# Power-Supplies.net
KiCad netlist of a schematic drawn in Altium Designer
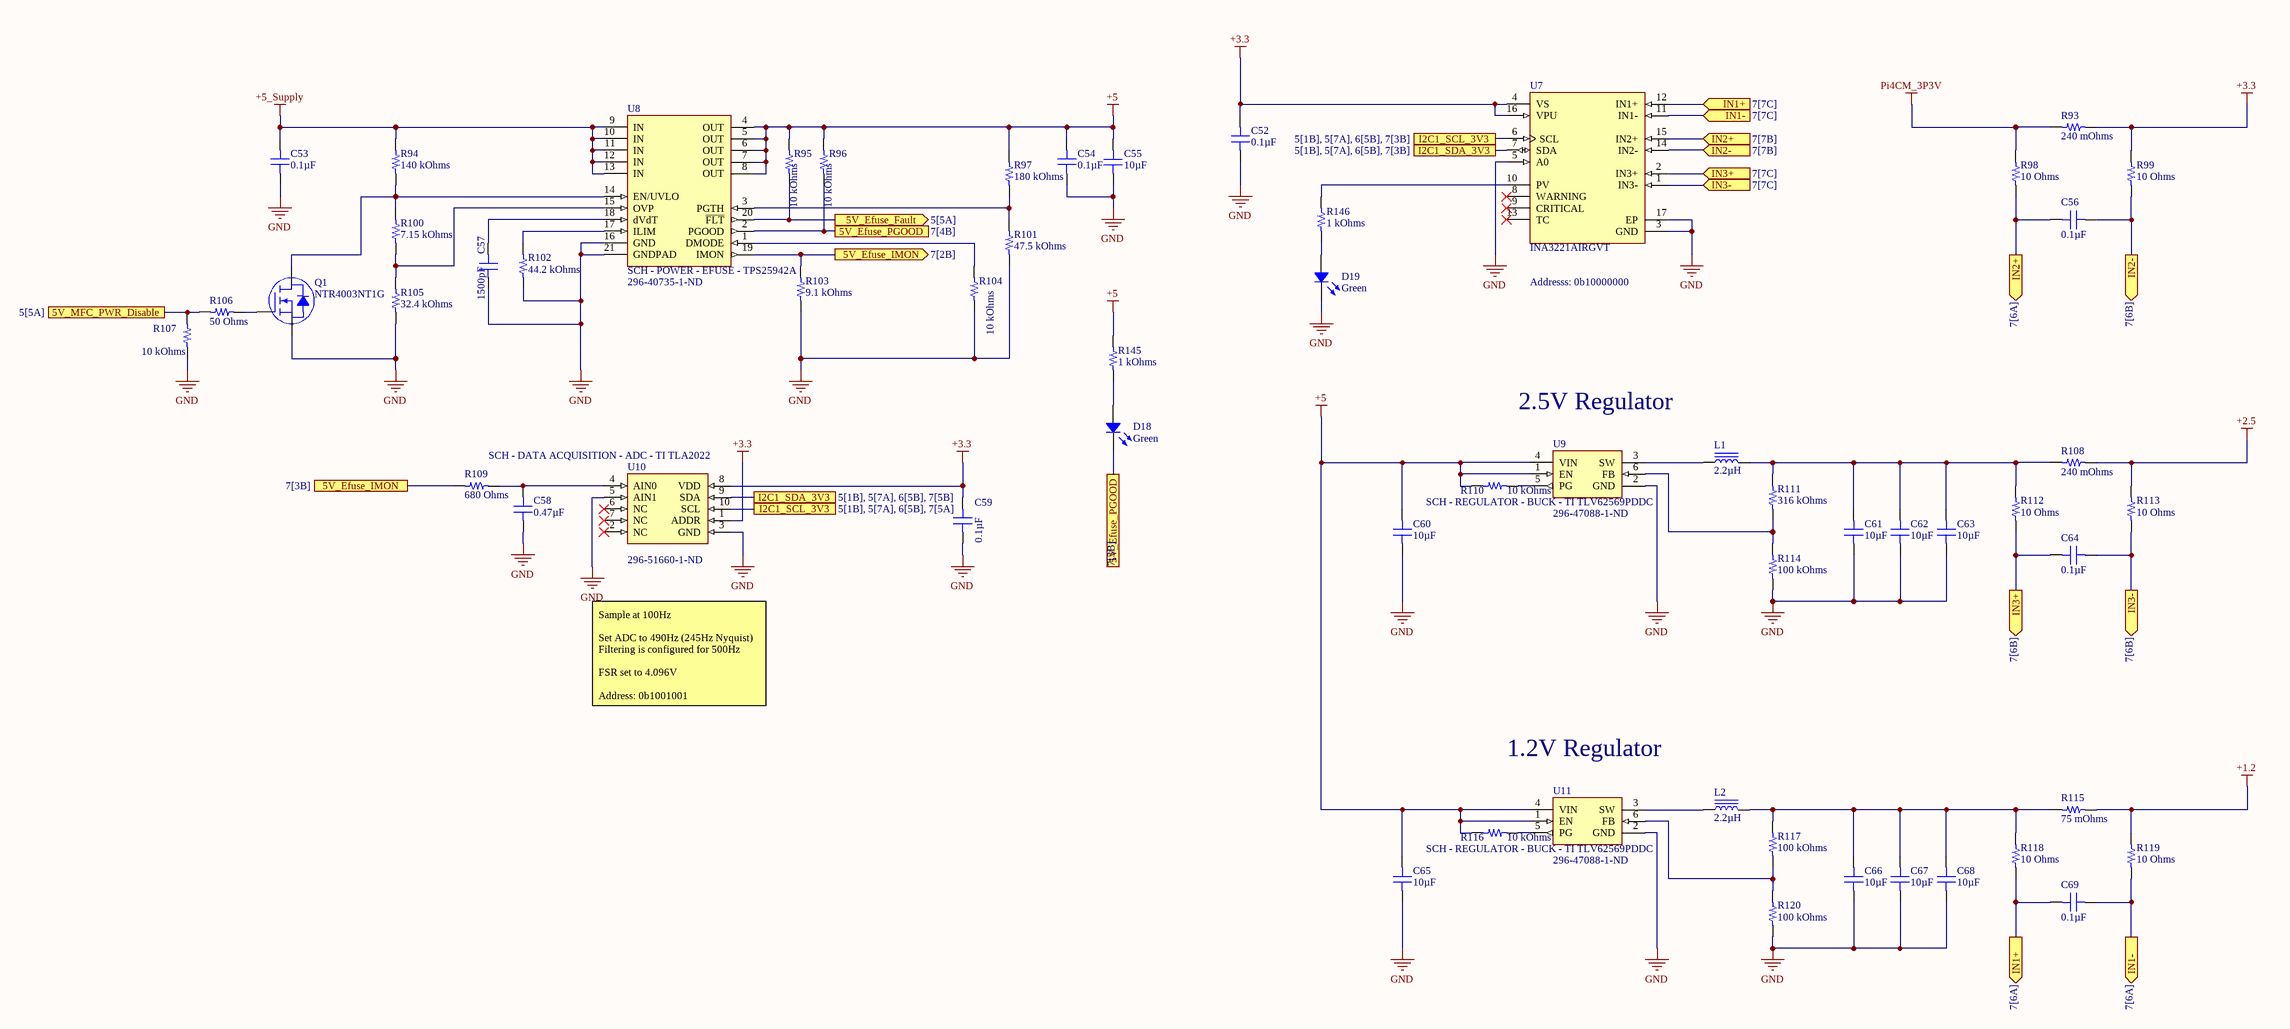
[diagram p0: Power-Supplies.SchDoc]

(export (version "E")
  (design (tool "Eeschema 10.0.6"))
  (components
    (comp (ref "C52")
      (value "0.1µF")
      (footprint "CAP 0603_1608")
      (description "CAP CER 0.1UF 25V X7R 0603")
      (fields
        (field (name "PART NUMBER") "CL10B104KA8WPNC")
        (field (name "MANUFACTURER") "Samsung Electro-Mechanics")
      )
      (libsource (lib "Celestial Altium Library - altium_library") (part "Capacitor"))
    )
    (comp (ref "C53")
      (value "0.1µF")
      (footprint "CAP 0603_1608")
      (description "CAP CER 0.1UF 25V X7R 0603")
      (fields
        (field (name "PART NUMBER") "CL10B104KA8WPNC")
        (field (name "MANUFACTURER") "Samsung Electro-Mechanics")
      )
      (libsource (lib "Celestial Altium Library - altium_library") (part "Capacitor"))
    )
    (comp (ref "C54")
      (value "0.1µF")
      (footprint "CAP 0603_1608")
      (description "CAP CER 0.1UF 25V X7R 0603")
      (fields
        (field (name "PART NUMBER") "CL10B104KA8WPNC")
        (field (name "MANUFACTURER") "Samsung Electro-Mechanics")
      )
      (libsource (lib "Celestial Altium Library - altium_library") (part "Capacitor"))
    )
    (comp (ref "C55")
      (value "10µF")
      (footprint "CAP 0805_2012")
      (description "CAP CER 10UF 16V X5R 0805")
      (fields (field (name "PART NUMBER") "CC0805KKX5R7BB106") (field (name "MANUFACTURER") "Yageo"))
      (libsource (lib "Celestial Altium Library - altium_library") (part "Capacitor"))
    )
    (comp (ref "C56")
      (value "0.1µF")
      (footprint "CAP 0603_1608")
      (description "CAP CER 0.1UF 25V X7R 0603")
      (fields
        (field (name "PART NUMBER") "CL10B104KA8WPNC")
        (field (name "MANUFACTURER") "Samsung Electro-Mechanics")
      )
      (libsource (lib "Celestial Altium Library - altium_library") (part "Capacitor"))
    )
    (comp (ref "C57")
      (value "1500pF")
      (footprint "CAP 0603_1608")
      (description "CAP CER 1500PF 25V X7R 0603")
      (fields (field (name "PART NUMBER") "CC0603JRX7R8BB152") (field (name "MANUFACTURER") "Yageo"))
      (libsource (lib "Celestial Altium Library - altium_library") (part "Capacitor"))
    )
    (comp (ref "C58")
      (value "0.47µF")
      (footprint "CAP 0603_1608")
      (description "CAP CER 0.47UF 16V X5R 0603")
      (fields (field (name "PART NUMBER") "C0603C474K4PACTU") (field (name "MANUFACTURER") "KEMET"))
      (libsource (lib "Celestial Altium Library - altium_library") (part "Capacitor"))
    )
    (comp (ref "C59")
      (value "0.1µF")
      (footprint "CAP 0603_1608")
      (description "CAP CER 0.1UF 25V X7R 0603")
      (fields
        (field (name "PART NUMBER") "CL10B104KA8WPNC")
        (field (name "MANUFACTURER") "Samsung Electro-Mechanics")
      )
      (libsource (lib "Celestial Altium Library - altium_library") (part "Capacitor"))
    )
    (comp (ref "C60")
      (value "10µF")
      (footprint "CAP 0805_2012")
      (description "CAP CER 10UF 16V X5R 0805")
      (fields (field (name "PART NUMBER") "CC0805KKX5R7BB106") (field (name "MANUFACTURER") "Yageo"))
      (libsource (lib "Celestial Altium Library - altium_library") (part "Capacitor"))
    )
    (comp (ref "C61")
      (value "10µF")
      (footprint "CAP 0805_2012")
      (description "CAP CER 10UF 16V X5R 0805")
      (fields (field (name "PART NUMBER") "CC0805KKX5R7BB106") (field (name "MANUFACTURER") "Yageo"))
      (libsource (lib "Celestial Altium Library - altium_library") (part "Capacitor"))
    )
    (comp (ref "C62")
      (value "10µF")
      (footprint "CAP 0805_2012")
      (description "CAP CER 10UF 16V X5R 0805")
      (fields (field (name "PART NUMBER") "CC0805KKX5R7BB106") (field (name "MANUFACTURER") "Yageo"))
      (libsource (lib "Celestial Altium Library - altium_library") (part "Capacitor"))
    )
    (comp (ref "C63")
      (value "10µF")
      (footprint "CAP 0805_2012")
      (description "CAP CER 10UF 16V X5R 0805")
      (fields (field (name "PART NUMBER") "CC0805KKX5R7BB106") (field (name "MANUFACTURER") "Yageo"))
      (libsource (lib "Celestial Altium Library - altium_library") (part "Capacitor"))
    )
    (comp (ref "C64")
      (value "0.1µF")
      (footprint "CAP 0603_1608")
      (description "CAP CER 0.1UF 25V X7R 0603")
      (fields
        (field (name "PART NUMBER") "CL10B104KA8WPNC")
        (field (name "MANUFACTURER") "Samsung Electro-Mechanics")
      )
      (libsource (lib "Celestial Altium Library - altium_library") (part "Capacitor"))
    )
    (comp (ref "C65")
      (value "10µF")
      (footprint "CAP 0805_2012")
      (description "CAP CER 10UF 16V X5R 0805")
      (fields (field (name "PART NUMBER") "CC0805KKX5R7BB106") (field (name "MANUFACTURER") "Yageo"))
      (libsource (lib "Celestial Altium Library - altium_library") (part "Capacitor"))
    )
    (comp (ref "C66")
      (value "10µF")
      (footprint "CAP 0805_2012")
      (description "CAP CER 10UF 16V X5R 0805")
      (fields (field (name "PART NUMBER") "CC0805KKX5R7BB106") (field (name "MANUFACTURER") "Yageo"))
      (libsource (lib "Celestial Altium Library - altium_library") (part "Capacitor"))
    )
    (comp (ref "C67")
      (value "10µF")
      (footprint "CAP 0805_2012")
      (description "CAP CER 10UF 16V X5R 0805")
      (fields (field (name "PART NUMBER") "CC0805KKX5R7BB106") (field (name "MANUFACTURER") "Yageo"))
      (libsource (lib "Celestial Altium Library - altium_library") (part "Capacitor"))
    )
    (comp (ref "C68")
      (value "10µF")
      (footprint "CAP 0805_2012")
      (description "CAP CER 10UF 16V X5R 0805")
      (fields (field (name "PART NUMBER") "CC0805KKX5R7BB106") (field (name "MANUFACTURER") "Yageo"))
      (libsource (lib "Celestial Altium Library - altium_library") (part "Capacitor"))
    )
    (comp (ref "C69")
      (value "0.1µF")
      (footprint "CAP 0603_1608")
      (description "CAP CER 0.1UF 25V X7R 0603")
      (fields
        (field (name "PART NUMBER") "CL10B104KA8WPNC")
        (field (name "MANUFACTURER") "Samsung Electro-Mechanics")
      )
      (libsource (lib "Celestial Altium Library - altium_library") (part "Capacitor"))
    )
    (comp (ref "D18")
      (value "Green")
      (footprint "LED 0603_1608 GREEN")
      (description "LED GREEN CLEAR CHIP SMD")
      (fields (field (name "PART NUMBER") "LTST-C193KGKT-5A") (field (name "MANUFACTURER") "Lite-On Inc."))
      (libsource (lib "Celestial Altium Library - altium_library") (part "LED"))
    )
    (comp (ref "D19")
      (value "Green")
      (footprint "LED 0603_1608 GREEN")
      (description "LED GREEN CLEAR CHIP SMD")
      (fields (field (name "PART NUMBER") "LTST-C193KGKT-5A") (field (name "MANUFACTURER") "Lite-On Inc."))
      (libsource (lib "Celestial Altium Library - altium_library") (part "LED"))
    )
    (comp (ref "L1")
      (value "2.2µH")
      (footprint "BOURNS SRN4018")
      (description "FIXED IND 2.2UH 2.9A 44 MOHM SMD")
      (fields (field (name "PART NUMBER") "SRN4018-2R2M") (field (name "MANUFACTURER") "Bourns Inc."))
      (libsource (lib "Celestial Altium Library - altium_library") (part "Inductor"))
    )
    (comp (ref "L2")
      (value "2.2µH")
      (footprint "BOURNS SRN4018")
      (description "FIXED IND 2.2UH 2.9A 44 MOHM SMD")
      (fields (field (name "PART NUMBER") "SRN4018-2R2M") (field (name "MANUFACTURER") "Bourns Inc."))
      (libsource (lib "Celestial Altium Library - altium_library") (part "Inductor"))
    )
    (comp (ref "Q1")
      (value "NTR4003NT1G")
      (footprint "ON SEMI SOT-23-3")
      (description "MOSFET N-CH 30V 500MA SOT-23")
      (fields (field (name "MANUFACTURER") "ON Semiconductor"))
      (libsource (lib "Celestial Altium Library - altium_library") (part "ON SEMI MOSFET N-CH SOT-23-3"))
    )
    (comp (ref "R93")
      (value "240 mOhms")
      (footprint "RES 0805_2012")
      (description "RES 240M OHM 1% 1/4W 0805")
      (fields (field (name "PART NUMBER") "KDV08FR240ET") (field (name "MANUFACTURER") "Ohmite"))
      (libsource (lib "Celestial Altium Library - altium_library") (part "Resistor"))
    )
    (comp (ref "R94")
      (value "140 kOhms")
      (footprint "RES 0603_1608")
      (description "RES SMD 140K OHM 0.1% 1/10W 0603")
      (fields (field (name "PART NUMBER") "RT0603BRE07140KL") (field (name "MANUFACTURER") "Yageo"))
      (libsource (lib "Celestial Altium Library - altium_library") (part "Resistor"))
    )
    (comp (ref "R95")
      (value "10 kOhms")
      (footprint "RES 0603_1608")
      (description "RES 10K OHM 5% 1/10W 0603")
      (fields
        (field (name "PART NUMBER") "RMCF0603JT10K0")
        (field (name "MANUFACTURER") "Stackpole Electronics Inc")
      )
      (libsource (lib "Celestial Altium Library - altium_library") (part "Resistor"))
    )
    (comp (ref "R96")
      (value "10 kOhms")
      (footprint "RES 0603_1608")
      (description "RES 10K OHM 5% 1/10W 0603")
      (fields
        (field (name "PART NUMBER") "RMCF0603JT10K0")
        (field (name "MANUFACTURER") "Stackpole Electronics Inc")
      )
      (libsource (lib "Celestial Altium Library - altium_library") (part "Resistor"))
    )
    (comp (ref "R97")
      (value "180 kOhms")
      (footprint "RES 0603_1608")
      (description "RES 180K OHM 1% 1/10W 0603")
      (fields
        (field (name "PART NUMBER") "RMCF0603FT180K")
        (field (name "MANUFACTURER") "Stackpole Electronics Inc")
      )
      (libsource (lib "Celestial Altium Library - altium_library") (part "Resistor"))
    )
    (comp (ref "R98")
      (value "10 Ohms")
      (footprint "RES 0603_1608")
      (description "CRGCQ 0603 10R 1%")
      (fields
        (field (name "PART NUMBER") "CRGCQ0603F10R")
        (field (name "MANUFACTURER") "TE Connectivity Passive Product")
      )
      (libsource (lib "Celestial Altium Library - altium_library") (part "Resistor"))
    )
    (comp (ref "R99")
      (value "10 Ohms")
      (footprint "RES 0603_1608")
      (description "CRGCQ 0603 10R 1%")
      (fields
        (field (name "PART NUMBER") "CRGCQ0603F10R")
        (field (name "MANUFACTURER") "TE Connectivity Passive Product")
      )
      (libsource (lib "Celestial Altium Library - altium_library") (part "Resistor"))
    )
    (comp (ref "R100")
      (value "7.15 kOhms")
      (footprint "RES 0603_1608")
      (description "RES SMD 7.15K OHM 0.1% 1/5W 0603")
      (fields
        (field (name "PART NUMBER") "ERJ-PB3B7151V")
        (field (name "MANUFACTURER") "Panasonic Electronic Components")
      )
      (libsource (lib "Celestial Altium Library - altium_library") (part "Resistor"))
    )
    (comp (ref "R101")
      (value "47.5 kOhms")
      (footprint "RES 0603_1608")
      (description "RES 47.5K OHM 1% 1/10W 0603")
      (fields
        (field (name "PART NUMBER") "RMCF0603FG47K5")
        (field (name "MANUFACTURER") "Stackpole Electronics Inc")
      )
      (libsource (lib "Celestial Altium Library - altium_library") (part "Resistor"))
    )
    (comp (ref "R102")
      (value "44.2 kOhms")
      (footprint "RES 0603_1608")
      (description "RES 44.2K OHM 1% 1/10W 0603")
      (fields
        (field (name "PART NUMBER") "RMCF0603FT44K2")
        (field (name "MANUFACTURER") "Stackpole Electronics Inc")
      )
      (libsource (lib "Celestial Altium Library - altium_library") (part "Resistor"))
    )
    (comp (ref "R103")
      (value "9.1 kOhms")
      (footprint "RES 0603_1608")
      (description "RES 9.1K OHM 1% 1/10W 0603")
      (fields
        (field (name "PART NUMBER") "RMCF0603FT9K10")
        (field (name "MANUFACTURER") "Stackpole Electronics Inc")
      )
      (libsource (lib "Celestial Altium Library - altium_library") (part "Resistor"))
    )
    (comp (ref "R104")
      (value "10 kOhms")
      (footprint "RES 0603_1608")
      (description "RES 10K OHM 5% 1/10W 0603")
      (fields
        (field (name "PART NUMBER") "RMCF0603JT10K0")
        (field (name "MANUFACTURER") "Stackpole Electronics Inc")
      )
      (libsource (lib "Celestial Altium Library - altium_library") (part "Resistor"))
    )
    (comp (ref "R105")
      (value "32.4 kOhms")
      (footprint "RES 0603_1608")
      (description "RES SMD 32.4K OHM 0.1% 1/5W 0603")
      (fields
        (field (name "PART NUMBER") "ERJ-PB3B3242V")
        (field (name "MANUFACTURER") "Panasonic Electronic Components")
      )
      (libsource (lib "Celestial Altium Library - altium_library") (part "Resistor"))
    )
    (comp (ref "R106")
      (value "50 Ohms")
      (footprint "RES 0603_1608")
      (description "RES SMD 50 OHM 1% 1/10W 0603")
      (fields (field (name "PART NUMBER") "CRCW060350R0FKEA") (field (name "MANUFACTURER") "Vishay Dale"))
      (libsource (lib "Celestial Altium Library - altium_library") (part "Resistor"))
    )
    (comp (ref "R107")
      (value "10 kOhms")
      (footprint "RES 0603_1608")
      (description "RES 10K OHM 5% 1/10W 0603")
      (fields
        (field (name "PART NUMBER") "RMCF0603JT10K0")
        (field (name "MANUFACTURER") "Stackpole Electronics Inc")
      )
      (libsource (lib "Celestial Altium Library - altium_library") (part "Resistor"))
    )
    (comp (ref "R108")
      (value "240 mOhms")
      (footprint "RES 0805_2012")
      (description "RES 240M OHM 1% 1/4W 0805")
      (fields (field (name "PART NUMBER") "KDV08FR240ET") (field (name "MANUFACTURER") "Ohmite"))
      (libsource (lib "Celestial Altium Library - altium_library") (part "Resistor"))
    )
    (comp (ref "R109")
      (value "680 Ohms")
      (footprint "RES 0603_1608")
      (description "RES 680 OHM 1% 1/10W 0603")
      (fields
        (field (name "PART NUMBER") "RMCF0603FT680R")
        (field (name "MANUFACTURER") "Stackpole Electronics Inc")
      )
      (libsource (lib "Celestial Altium Library - altium_library") (part "Resistor"))
    )
    (comp (ref "R110")
      (value "10 kOhms")
      (footprint "RES 0603_1608")
      (description "RES 10K OHM 5% 1/10W 0603")
      (fields
        (field (name "PART NUMBER") "RMCF0603JT10K0")
        (field (name "MANUFACTURER") "Stackpole Electronics Inc")
      )
      (libsource (lib "Celestial Altium Library - altium_library") (part "Resistor"))
    )
    (comp (ref "R111")
      (value "316 kOhms")
      (footprint "RES 0603_1608")
      (description "RES 316K OHM 1% 1/10W 0603")
      (fields
        (field (name "PART NUMBER") "RMCF0603FT316K")
        (field (name "MANUFACTURER") "Stackpole Electronics Inc")
      )
      (libsource (lib "Celestial Altium Library - altium_library") (part "Resistor"))
    )
    (comp (ref "R112")
      (value "10 Ohms")
      (footprint "RES 0603_1608")
      (description "CRGCQ 0603 10R 1%")
      (fields
        (field (name "PART NUMBER") "CRGCQ0603F10R")
        (field (name "MANUFACTURER") "TE Connectivity Passive Product")
      )
      (libsource (lib "Celestial Altium Library - altium_library") (part "Resistor"))
    )
    (comp (ref "R113")
      (value "10 Ohms")
      (footprint "RES 0603_1608")
      (description "CRGCQ 0603 10R 1%")
      (fields
        (field (name "PART NUMBER") "CRGCQ0603F10R")
        (field (name "MANUFACTURER") "TE Connectivity Passive Product")
      )
      (libsource (lib "Celestial Altium Library - altium_library") (part "Resistor"))
    )
    (comp (ref "R114")
      (value "100 kOhms")
      (footprint "RES 0603_1608")
      (description "RES 100K OHM 1% 1/10W 0603")
      (fields
        (field (name "PART NUMBER") "RMCF0603FT100K")
        (field (name "MANUFACTURER") "Stackpole Electronics Inc")
      )
      (libsource (lib "Celestial Altium Library - altium_library") (part "Resistor"))
    )
    (comp (ref "R115")
      (value "75 mOhms")
      (footprint "RES 0805_2012")
      (description "RES 0.075 OHM 1% 1/4W 0805")
      (fields
        (field (name "PART NUMBER") "ERJ-L06UF75MV")
        (field (name "MANUFACTURER") "Panasonic Electronic Components")
      )
      (libsource (lib "Celestial Altium Library - altium_library") (part "Resistor"))
    )
    (comp (ref "R116")
      (value "10 kOhms")
      (footprint "RES 0603_1608")
      (description "RES 10K OHM 5% 1/10W 0603")
      (fields
        (field (name "PART NUMBER") "RMCF0603JT10K0")
        (field (name "MANUFACTURER") "Stackpole Electronics Inc")
      )
      (libsource (lib "Celestial Altium Library - altium_library") (part "Resistor"))
    )
    (comp (ref "R117")
      (value "100 kOhms")
      (footprint "RES 0603_1608")
      (description "RES 100K OHM 1% 1/10W 0603")
      (fields
        (field (name "PART NUMBER") "RMCF0603FT100K")
        (field (name "MANUFACTURER") "Stackpole Electronics Inc")
      )
      (libsource (lib "Celestial Altium Library - altium_library") (part "Resistor"))
    )
    (comp (ref "R118")
      (value "10 Ohms")
      (footprint "RES 0603_1608")
      (description "CRGCQ 0603 10R 1%")
      (fields
        (field (name "PART NUMBER") "CRGCQ0603F10R")
        (field (name "MANUFACTURER") "TE Connectivity Passive Product")
      )
      (libsource (lib "Celestial Altium Library - altium_library") (part "Resistor"))
    )
    (comp (ref "R119")
      (value "10 Ohms")
      (footprint "RES 0603_1608")
      (description "CRGCQ 0603 10R 1%")
      (fields
        (field (name "PART NUMBER") "CRGCQ0603F10R")
        (field (name "MANUFACTURER") "TE Connectivity Passive Product")
      )
      (libsource (lib "Celestial Altium Library - altium_library") (part "Resistor"))
    )
    (comp (ref "R120")
      (value "100 kOhms")
      (footprint "RES 0603_1608")
      (description "RES 100K OHM 1% 1/10W 0603")
      (fields
        (field (name "PART NUMBER") "RMCF0603FT100K")
        (field (name "MANUFACTURER") "Stackpole Electronics Inc")
      )
      (libsource (lib "Celestial Altium Library - altium_library") (part "Resistor"))
    )
    (comp (ref "R145")
      (value "1 kOhms")
      (footprint "RES 0603_1608")
      (description "RES 1K OHM 1% 1/8W 0603")
      (fields
        (field (name "PART NUMBER") "RNCP0603FTD1K00")
        (field (name "MANUFACTURER") "Stackpole Electronics Inc")
      )
      (libsource (lib "Celestial Altium Library - altium_library") (part "Resistor"))
    )
    (comp (ref "R146")
      (value "1 kOhms")
      (footprint "RES 0603_1608")
      (description "RES 1K OHM 1% 1/8W 0603")
      (fields
        (field (name "PART NUMBER") "RNCP0603FTD1K00")
        (field (name "MANUFACTURER") "Stackpole Electronics Inc")
      )
      (libsource (lib "Celestial Altium Library - altium_library") (part "Resistor"))
    )
    (comp (ref "U7")
      (value "INA3221AIRGVT")
      (footprint "RGV0016A_V")
      (fields (field (name "MANUFACTURER") "Texas Instruments"))
      (libsource (lib "Altium Content Vault") (part "TI-INA3221-RGV-16"))
    )
    (comp (ref "U8")
      (value "SCH - POWER - EFUSE - TPS25942A")
      (footprint "PCB - LEADLESS - QFN - TI 20-WQFN")
      (fields (field (name "SUPPLIER PART NUMBER 1") "296-40735-1-ND"))
      (libsource (lib "HAB_ICs") (part "SCH - POWER - EFUSE - TPS25942A"))
    )
    (comp (ref "U9")
      (value "SCH - REGULATOR - BUCK - TI TLV62569PDDC")
      (footprint "PCB - LEADS - SOT- TI TSOT-23-6")
      (fields (field (name "SUPPLIER PART NUMBER 1") "296-47088-1-ND"))
      (libsource (lib "HAB_ICs") (part "SCH - REGULATOR - BUCK - TI TLV62569PDDC"))
    )
    (comp (ref "U10")
      (value "SCH - DATA ACQUISITION - ADC - TI TLA2022")
      (footprint "PCB - LEADLESS - QFN - TI X2QFN-10")
      (fields (field (name "SUPPLIER PART NUMBER 1") "296-51660-1-ND"))
      (libsource (lib "HAB_ICs") (part "SCH - DATA ACQUISITION - ADC - TI TLA2022"))
    )
    (comp (ref "U11")
      (value "SCH - REGULATOR - BUCK - TI TLV62569PDDC")
      (footprint "PCB - LEADS - SOT- TI TSOT-23-6")
      (fields (field (name "SUPPLIER PART NUMBER 1") "296-47088-1-ND"))
      (libsource (lib "HAB_ICs") (part "SCH - REGULATOR - BUCK - TI TLV62569PDDC"))
    )
  )
  (nets
    (net (code "1") (name "+1.2") (class "Default")
      (node (ref "R115") (pin "2") (pinfunction "2_2") (pintype "passive"))
      (node (ref "R119") (pin "2") (pinfunction "2_2") (pintype "passive"))
    )
    (net (code "2") (name "+2.5") (class "Default")
      (node (ref "R108") (pin "2") (pinfunction "2_2") (pintype "passive"))
      (node (ref "R113") (pin "2") (pinfunction "2_2") (pintype "passive"))
    )
    (net (code "3") (name "+3.3") (class "Default")
      (node (ref "C52") (pin "2") (pinfunction "2_2") (pintype "passive"))
      (node (ref "C59") (pin "2") (pinfunction "2_2") (pintype "passive"))
      (node (ref "R93") (pin "2") (pinfunction "2_2") (pintype "passive"))
      (node (ref "R99") (pin "2") (pinfunction "2_2") (pintype "passive"))
      (node (ref "U10") (pin "1") (pinfunction "ADDR_1") (pintype "input"))
      (node (ref "U10") (pin "8") (pinfunction "VDD_8") (pintype "input"))
      (node (ref "U7") (pin "16") (pinfunction "VPU_16") (pintype "input"))
      (node (ref "U7") (pin "4") (pinfunction "VS_4") (pintype "power_in"))
    )
    (net (code "4") (name "+5") (class "Default")
      (node (ref "C54") (pin "2") (pinfunction "2_2") (pintype "passive"))
      (node (ref "C55") (pin "2") (pinfunction "2_2") (pintype "passive"))
      (node (ref "C60") (pin "2") (pinfunction "2_2") (pintype "passive"))
      (node (ref "C65") (pin "2") (pinfunction "2_2") (pintype "passive"))
      (node (ref "R110") (pin "2") (pinfunction "2_2") (pintype "passive"))
      (node (ref "R116") (pin "2") (pinfunction "2_2") (pintype "passive"))
      (node (ref "R145") (pin "1") (pinfunction "1_1") (pintype "passive"))
      (node (ref "R95") (pin "2") (pinfunction "2_2") (pintype "passive"))
      (node (ref "R96") (pin "2") (pinfunction "2_2") (pintype "passive"))
      (node (ref "R97") (pin "2") (pinfunction "2_2") (pintype "passive"))
      (node (ref "U11") (pin "1") (pinfunction "EN_1") (pintype "input"))
      (node (ref "U11") (pin "4") (pinfunction "VIN_4") (pintype "power_in"))
      (node (ref "U8") (pin "4") (pinfunction "OUT_4") (pintype "power_in"))
      (node (ref "U8") (pin "5") (pinfunction "OUT_5") (pintype "power_in"))
      (node (ref "U8") (pin "6") (pinfunction "OUT_6") (pintype "power_in"))
      (node (ref "U8") (pin "7") (pinfunction "OUT_7") (pintype "power_in"))
      (node (ref "U8") (pin "8") (pinfunction "OUT_8") (pintype "power_in"))
      (node (ref "U9") (pin "1") (pinfunction "EN_1") (pintype "input"))
      (node (ref "U9") (pin "4") (pinfunction "VIN_4") (pintype "power_in"))
    )
    (net (code "5") (name "+5_Supply") (class "Default")
      (node (ref "C53") (pin "2") (pinfunction "2_2") (pintype "passive"))
      (node (ref "R94") (pin "2") (pinfunction "2_2") (pintype "passive"))
      (node (ref "U8") (pin "10") (pinfunction "IN_10") (pintype "power_in"))
      (node (ref "U8") (pin "11") (pinfunction "IN_11") (pintype "power_in"))
      (node (ref "U8") (pin "12") (pinfunction "IN_12") (pintype "power_in"))
      (node (ref "U8") (pin "13") (pinfunction "IN_13") (pintype "power_in"))
      (node (ref "U8") (pin "9") (pinfunction "IN_9") (pintype "power_in"))
    )
    (net (code "6") (name "/5V_Efuse_Fault") (class "Default")
      (node (ref "R95") (pin "1") (pinfunction "1_1") (pintype "passive"))
      (node (ref "U8") (pin "20") (pinfunction "~{FLT}_20") (pintype "output"))
    )
    (net (code "7") (name "/5V_Efuse_IMON") (class "Default")
      (node (ref "R103") (pin "2") (pinfunction "2_2") (pintype "passive"))
      (node (ref "R109") (pin "1") (pinfunction "1_1") (pintype "passive"))
      (node (ref "U8") (pin "19") (pinfunction "IMON_19") (pintype "output"))
    )
    (net (code "8") (name "/5V_Efuse_PGOOD") (class "Default")
      (node (ref "D18") (pin "2") (pinfunction "2_2") (pintype "passive"))
      (node (ref "R96") (pin "1") (pinfunction "1_1") (pintype "passive"))
      (node (ref "U8") (pin "2") (pinfunction "PGOOD_2") (pintype "output"))
    )
    (net (code "9") (name "/5V_MFC_PWR_Disable") (class "Default")
      (node (ref "R106") (pin "2") (pinfunction "2_2") (pintype "passive"))
      (node (ref "R107") (pin "2") (pinfunction "2_2") (pintype "passive"))
    )
    (net (code "10") (name "/I2C1_SCL_3V3") (class "Default")
      (node (ref "U10") (pin "10") (pinfunction "SCL_10") (pintype "input"))
      (node (ref "U7") (pin "6") (pinfunction "SCL_6") (pintype "input"))
    )
    (net (code "11") (name "/I2C1_SDA_3V3") (class "Default")
      (node (ref "U10") (pin "9") (pinfunction "SDA_9") (pintype "input"))
      (node (ref "U7") (pin "7") (pinfunction "SDA_7") (pintype "bidirectional"))
    )
    (net (code "12") (name "/IN1+") (class "Default")
      (node (ref "C69") (pin "2") (pinfunction "2_2") (pintype "passive"))
      (node (ref "R118") (pin "1") (pinfunction "1_1") (pintype "passive"))
      (node (ref "U7") (pin "12") (pinfunction "IN1+_12") (pintype "input"))
    )
    (net (code "13") (name "/IN1-") (class "Default")
      (node (ref "C69") (pin "1") (pinfunction "1_1") (pintype "passive"))
      (node (ref "R119") (pin "1") (pinfunction "1_1") (pintype "passive"))
      (node (ref "U7") (pin "11") (pinfunction "IN1-_11") (pintype "input"))
    )
    (net (code "14") (name "/IN2+") (class "Default")
      (node (ref "C56") (pin "2") (pinfunction "2_2") (pintype "passive"))
      (node (ref "R98") (pin "1") (pinfunction "1_1") (pintype "passive"))
      (node (ref "U7") (pin "15") (pinfunction "IN2+_15") (pintype "input"))
    )
    (net (code "15") (name "/IN2-") (class "Default")
      (node (ref "C56") (pin "1") (pinfunction "1_1") (pintype "passive"))
      (node (ref "R99") (pin "1") (pinfunction "1_1") (pintype "passive"))
      (node (ref "U7") (pin "14") (pinfunction "IN2-_14") (pintype "input"))
    )
    (net (code "16") (name "/IN3+") (class "Default")
      (node (ref "C64") (pin "2") (pinfunction "2_2") (pintype "passive"))
      (node (ref "R112") (pin "1") (pinfunction "1_1") (pintype "passive"))
      (node (ref "U7") (pin "2") (pinfunction "IN3+_2") (pintype "input"))
    )
    (net (code "17") (name "/IN3-") (class "Default")
      (node (ref "C64") (pin "1") (pinfunction "1_1") (pintype "passive"))
      (node (ref "R113") (pin "1") (pinfunction "1_1") (pintype "passive"))
      (node (ref "U7") (pin "1") (pinfunction "IN3-_1") (pintype "input"))
    )
    (net (code "18") (name "GND") (class "Default")
      (node (ref "C52") (pin "1") (pinfunction "1_1") (pintype "passive"))
      (node (ref "C53") (pin "1") (pinfunction "1_1") (pintype "passive"))
      (node (ref "C54") (pin "1") (pinfunction "1_1") (pintype "passive"))
      (node (ref "C55") (pin "1") (pinfunction "1_1") (pintype "passive"))
      (node (ref "C57") (pin "1") (pinfunction "1_1") (pintype "passive"))
      (node (ref "C58") (pin "1") (pinfunction "1_1") (pintype "passive"))
      (node (ref "C59") (pin "1") (pinfunction "1_1") (pintype "passive"))
      (node (ref "C60") (pin "1") (pinfunction "1_1") (pintype "passive"))
      (node (ref "C61") (pin "1") (pinfunction "1_1") (pintype "passive"))
      (node (ref "C62") (pin "1") (pinfunction "1_1") (pintype "passive"))
      (node (ref "C63") (pin "1") (pinfunction "1_1") (pintype "passive"))
      (node (ref "C65") (pin "1") (pinfunction "1_1") (pintype "passive"))
      (node (ref "C66") (pin "1") (pinfunction "1_1") (pintype "passive"))
      (node (ref "C67") (pin "1") (pinfunction "1_1") (pintype "passive"))
      (node (ref "C68") (pin "1") (pinfunction "1_1") (pintype "passive"))
      (node (ref "D19") (pin "2") (pinfunction "2_2") (pintype "passive"))
      (node (ref "Q1") (pin "2") (pinfunction "S_2") (pintype "passive"))
      (node (ref "R101") (pin "1") (pinfunction "1_1") (pintype "passive"))
      (node (ref "R102") (pin "1") (pinfunction "1_1") (pintype "passive"))
      (node (ref "R103") (pin "1") (pinfunction "1_1") (pintype "passive"))
      (node (ref "R104") (pin "1") (pinfunction "1_1") (pintype "passive"))
      (node (ref "R105") (pin "1") (pinfunction "1_1") (pintype "passive"))
      (node (ref "R107") (pin "1") (pinfunction "1_1") (pintype "passive"))
      (node (ref "R114") (pin "1") (pinfunction "1_1") (pintype "passive"))
      (node (ref "R120") (pin "1") (pinfunction "1_1") (pintype "passive"))
      (node (ref "U10") (pin "3") (pinfunction "GND_3") (pintype "input"))
      (node (ref "U10") (pin "5") (pinfunction "AIN1_5") (pintype "input"))
      (node (ref "U11") (pin "2") (pinfunction "GND_2") (pintype "power_in"))
      (node (ref "U7") (pin "17") (pinfunction "EP_17") (pintype "passive"))
      (node (ref "U7") (pin "3") (pinfunction "GND_3") (pintype "power_in"))
      (node (ref "U7") (pin "5") (pinfunction "A0_5") (pintype "input"))
      (node (ref "U8") (pin "16") (pinfunction "GND_16") (pintype "power_in"))
      (node (ref "U8") (pin "21") (pinfunction "GNDPAD_21") (pintype "power_in"))
      (node (ref "U9") (pin "2") (pinfunction "GND_2") (pintype "power_in"))
    )
    (net (code "19") (name "Net-(C61-Pad2)") (class "Default")
      (node (ref "C61") (pin "2") (pinfunction "2_2") (pintype "passive"))
      (node (ref "C62") (pin "2") (pinfunction "2_2") (pintype "passive"))
      (node (ref "C63") (pin "2") (pinfunction "2_2") (pintype "passive"))
      (node (ref "L1") (pin "2") (pinfunction "2_2") (pintype "passive"))
      (node (ref "R108") (pin "1") (pinfunction "1_1") (pintype "passive"))
      (node (ref "R111") (pin "2") (pinfunction "2_2") (pintype "passive"))
      (node (ref "R112") (pin "2") (pinfunction "2_2") (pintype "passive"))
    )
    (net (code "20") (name "Net-(C66-Pad2)") (class "Default")
      (node (ref "C66") (pin "2") (pinfunction "2_2") (pintype "passive"))
      (node (ref "C67") (pin "2") (pinfunction "2_2") (pintype "passive"))
      (node (ref "C68") (pin "2") (pinfunction "2_2") (pintype "passive"))
      (node (ref "L2") (pin "2") (pinfunction "2_2") (pintype "passive"))
      (node (ref "R115") (pin "1") (pinfunction "1_1") (pintype "passive"))
      (node (ref "R117") (pin "2") (pinfunction "2_2") (pintype "passive"))
      (node (ref "R118") (pin "2") (pinfunction "2_2") (pintype "passive"))
    )
    (net (code "21") (name "Net-(D18-Pad1)") (class "Default")
      (node (ref "D18") (pin "1") (pinfunction "1_1") (pintype "passive"))
      (node (ref "R145") (pin "2") (pinfunction "2_2") (pintype "passive"))
    )
    (net (code "22") (name "Net-(D19-Pad1)") (class "Default")
      (node (ref "D19") (pin "1") (pinfunction "1_1") (pintype "passive"))
      (node (ref "R146") (pin "1") (pinfunction "1_1") (pintype "passive"))
    )
    (net (code "23") (name "Net-(Q1-D)") (class "Default")
      (node (ref "Q1") (pin "3") (pinfunction "D_3") (pintype "passive"))
      (node (ref "R100") (pin "2") (pinfunction "2_2") (pintype "passive"))
      (node (ref "R94") (pin "1") (pinfunction "1_1") (pintype "passive"))
      (node (ref "U8") (pin "14") (pinfunction "EN/UVLO_14") (pintype "input"))
    )
    (net (code "24") (name "Net-(Q1-G)") (class "Default")
      (node (ref "Q1") (pin "1") (pinfunction "G_1") (pintype "passive"))
      (node (ref "R106") (pin "1") (pinfunction "1_1") (pintype "passive"))
    )
    (net (code "25") (name "Net-(U7-PV)") (class "Default")
      (node (ref "R146") (pin "2") (pinfunction "2_2") (pintype "passive"))
      (node (ref "U7") (pin "10") (pinfunction "PV_10") (pintype "open_collector"))
    )
    (net (code "26") (name "Net-(U8-DMODE)") (class "Default")
      (node (ref "R104") (pin "2") (pinfunction "2_2") (pintype "passive"))
      (node (ref "U8") (pin "1") (pinfunction "DMODE_1") (pintype "input"))
    )
    (net (code "27") (name "Net-(U8-ILIM)") (class "Default")
      (node (ref "R102") (pin "2") (pinfunction "2_2") (pintype "passive"))
      (node (ref "U8") (pin "17") (pinfunction "ILIM_17") (pintype "input"))
    )
    (net (code "28") (name "Net-(U8-OVP)") (class "Default")
      (node (ref "R100") (pin "1") (pinfunction "1_1") (pintype "passive"))
      (node (ref "R105") (pin "2") (pinfunction "2_2") (pintype "passive"))
      (node (ref "U8") (pin "15") (pinfunction "OVP_15") (pintype "input"))
    )
    (net (code "29") (name "Net-(U8-PGTH)") (class "Default")
      (node (ref "R101") (pin "2") (pinfunction "2_2") (pintype "passive"))
      (node (ref "R97") (pin "1") (pinfunction "1_1") (pintype "passive"))
      (node (ref "U8") (pin "3") (pinfunction "PGTH_3") (pintype "input"))
    )
    (net (code "30") (name "Net-(U8-dVdT)") (class "Default")
      (node (ref "C57") (pin "2") (pinfunction "2_2") (pintype "passive"))
      (node (ref "U8") (pin "18") (pinfunction "dVdT_18") (pintype "input"))
    )
    (net (code "31") (name "Net-(U9-FB)") (class "Default")
      (node (ref "R111") (pin "1") (pinfunction "1_1") (pintype "passive"))
      (node (ref "R114") (pin "2") (pinfunction "2_2") (pintype "passive"))
      (node (ref "U9") (pin "6") (pinfunction "FB_6") (pintype "input"))
    )
    (net (code "32") (name "Net-(U9-PG)") (class "Default")
      (node (ref "R110") (pin "1") (pinfunction "1_1") (pintype "passive"))
      (node (ref "U9") (pin "5") (pinfunction "PG_5") (pintype "output"))
    )
    (net (code "33") (name "Net-(U9-SW)") (class "Default")
      (node (ref "L1") (pin "1") (pinfunction "1_1") (pintype "passive"))
      (node (ref "U9") (pin "3") (pinfunction "SW_3") (pintype "power_in"))
    )
    (net (code "34") (name "Net-(U10-AIN0)") (class "Default")
      (node (ref "C58") (pin "2") (pinfunction "2_2") (pintype "passive"))
      (node (ref "R109") (pin "2") (pinfunction "2_2") (pintype "passive"))
      (node (ref "U10") (pin "4") (pinfunction "AIN0_4") (pintype "input"))
    )
    (net (code "35") (name "Net-(U11-FB)") (class "Default")
      (node (ref "R117") (pin "1") (pinfunction "1_1") (pintype "passive"))
      (node (ref "R120") (pin "2") (pinfunction "2_2") (pintype "passive"))
      (node (ref "U11") (pin "6") (pinfunction "FB_6") (pintype "input"))
    )
    (net (code "36") (name "Net-(U11-PG)") (class "Default")
      (node (ref "R116") (pin "1") (pinfunction "1_1") (pintype "passive"))
      (node (ref "U11") (pin "5") (pinfunction "PG_5") (pintype "output"))
    )
    (net (code "37") (name "Net-(U11-SW)") (class "Default")
      (node (ref "L2") (pin "1") (pinfunction "1_1") (pintype "passive"))
      (node (ref "U11") (pin "3") (pinfunction "SW_3") (pintype "power_in"))
    )
    (net (code "38") (name "Pi4CM_3P3V") (class "Default")
      (node (ref "R93") (pin "1") (pinfunction "1_1") (pintype "passive"))
      (node (ref "R98") (pin "2") (pinfunction "2_2") (pintype "passive"))
    )
    (net (code "39") (name "unconnected-(U7-CRITICAL-Pad9)") (class "Default")
      (node (ref "U7") (pin "9") (pinfunction "CRITICAL_9") (pintype "open_collector+no_connect"))
    )
    (net (code "40") (name "unconnected-(U7-TC-Pad13)") (class "Default")
      (node (ref "U7") (pin "13") (pinfunction "TC_13") (pintype "open_collector+no_connect"))
    )
    (net (code "41") (name "unconnected-(U7-WARNING-Pad8)") (class "Default")
      (node (ref "U7") (pin "8") (pinfunction "WARNING_8") (pintype "open_collector+no_connect"))
    )
    (net (code "42") (name "unconnected-(U10-NC-Pad2)") (class "Default")
      (node (ref "U10") (pin "2") (pinfunction "NC_2") (pintype "input+no_connect"))
    )
    (net (code "43") (name "unconnected-(U10-NC-Pad6)") (class "Default")
      (node (ref "U10") (pin "6") (pinfunction "NC_6") (pintype "input+no_connect"))
    )
    (net (code "44") (name "unconnected-(U10-NC-Pad7)") (class "Default")
      (node (ref "U10") (pin "7") (pinfunction "NC_7") (pintype "input+no_connect"))
    )
  )
)
